# konektor_zas.net
KiCad netlist of a schematic drawn in EAGLE
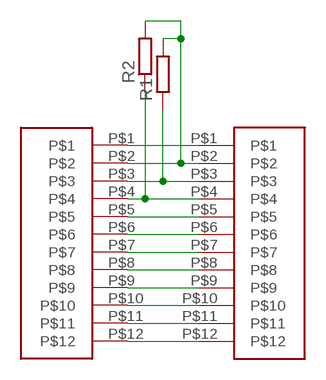
[diagram p0: schematic, sheet 1]

(export (version "E")
  (design (tool "Eeschema 10.0.6"))
  (components
    (comp (ref "R1")
      (value "R-EU_R0805")
      (footprint "eagle-import:R0805")
      (libsource (lib "eagle-import") (part "R-EU_R0805"))
    )
    (comp (ref "R2")
      (value "R-EU_R0805")
      (footprint "eagle-import:R0805")
      (libsource (lib "eagle-import") (part "R-EU_R0805"))
    )
    (comp (ref "U$1")
      (value "12PINCON")
      (footprint "eagle-import:12PIN2MMCON")
      (libsource (lib "eagle-import") (part "12PINCON"))
    )
    (comp (ref "U$2")
      (value "12PINCON")
      (footprint "eagle-import:12PIN2MMCON")
      (libsource (lib "eagle-import") (part "12PINCON"))
    )
  )
  (nets
    (net (code "1") (name "Net-(R1-Pad1)") (class "Default")
      (node (ref "R1") (pin "1") (pinfunction "1_1") (pintype "passive"))
      (node (ref "U$1") (pin "P$3") (pinfunction "P$3_P$3") (pintype "bidirectional"))
      (node (ref "U$2") (pin "P$3") (pinfunction "P$3_P$3") (pintype "bidirectional"))
    )
    (net (code "2") (name "Net-(R1-Pad2)") (class "Default")
      (node (ref "R1") (pin "2") (pinfunction "2_2") (pintype "passive"))
      (node (ref "R2") (pin "2") (pinfunction "2_2") (pintype "passive"))
      (node (ref "U$1") (pin "P$2") (pinfunction "P$2_P$2") (pintype "bidirectional"))
      (node (ref "U$2") (pin "P$2") (pinfunction "P$2_P$2") (pintype "bidirectional"))
    )
    (net (code "3") (name "Net-(R2-Pad1)") (class "Default")
      (node (ref "R2") (pin "1") (pinfunction "1_1") (pintype "passive"))
      (node (ref "U$1") (pin "P$4") (pinfunction "P$4_P$4") (pintype "bidirectional"))
      (node (ref "U$2") (pin "P$4") (pinfunction "P$4_P$4") (pintype "bidirectional"))
    )
    (net (code "4") (name "Net-(U$1-PadP$1)") (class "Default")
      (node (ref "U$1") (pin "P$1") (pinfunction "P$1_P$1") (pintype "bidirectional"))
      (node (ref "U$2") (pin "P$1") (pinfunction "P$1_P$1") (pintype "bidirectional"))
    )
    (net (code "5") (name "Net-(U$1-PadP$5)") (class "Default")
      (node (ref "U$1") (pin "P$5") (pinfunction "P$5_P$5") (pintype "bidirectional"))
      (node (ref "U$2") (pin "P$5") (pinfunction "P$5_P$5") (pintype "bidirectional"))
    )
    (net (code "6") (name "Net-(U$1-PadP$6)") (class "Default")
      (node (ref "U$1") (pin "P$6") (pinfunction "P$6_P$6") (pintype "bidirectional"))
      (node (ref "U$2") (pin "P$6") (pinfunction "P$6_P$6") (pintype "bidirectional"))
    )
    (net (code "7") (name "Net-(U$1-PadP$7)") (class "Default")
      (node (ref "U$1") (pin "P$7") (pinfunction "P$7_P$7") (pintype "bidirectional"))
      (node (ref "U$2") (pin "P$7") (pinfunction "P$7_P$7") (pintype "bidirectional"))
    )
    (net (code "8") (name "Net-(U$1-PadP$8)") (class "Default")
      (node (ref "U$1") (pin "P$8") (pinfunction "P$8_P$8") (pintype "bidirectional"))
      (node (ref "U$2") (pin "P$8") (pinfunction "P$8_P$8") (pintype "bidirectional"))
    )
    (net (code "9") (name "Net-(U$1-PadP$9)") (class "Default")
      (node (ref "U$1") (pin "P$9") (pinfunction "P$9_P$9") (pintype "bidirectional"))
      (node (ref "U$2") (pin "P$9") (pinfunction "P$9_P$9") (pintype "bidirectional"))
    )
    (net (code "10") (name "Net-(U$1-PadP$10)") (class "Default")
      (node (ref "U$1") (pin "P$10") (pinfunction "P$10_P$10") (pintype "bidirectional"))
      (node (ref "U$2") (pin "P$10") (pinfunction "P$10_P$10") (pintype "bidirectional"))
    )
    (net (code "11") (name "Net-(U$1-PadP$11)") (class "Default")
      (node (ref "U$1") (pin "P$11") (pinfunction "P$11_P$11") (pintype "bidirectional"))
      (node (ref "U$2") (pin "P$11") (pinfunction "P$11_P$11") (pintype "bidirectional"))
    )
    (net (code "12") (name "Net-(U$1-PadP$12)") (class "Default")
      (node (ref "U$1") (pin "P$12") (pinfunction "P$12_P$12") (pintype "bidirectional"))
      (node (ref "U$2") (pin "P$12") (pinfunction "P$12_P$12") (pintype "bidirectional"))
    )
  )
)
